# Schematic_328programmer.net
KiCad netlist of a schematic drawn in EAGLE
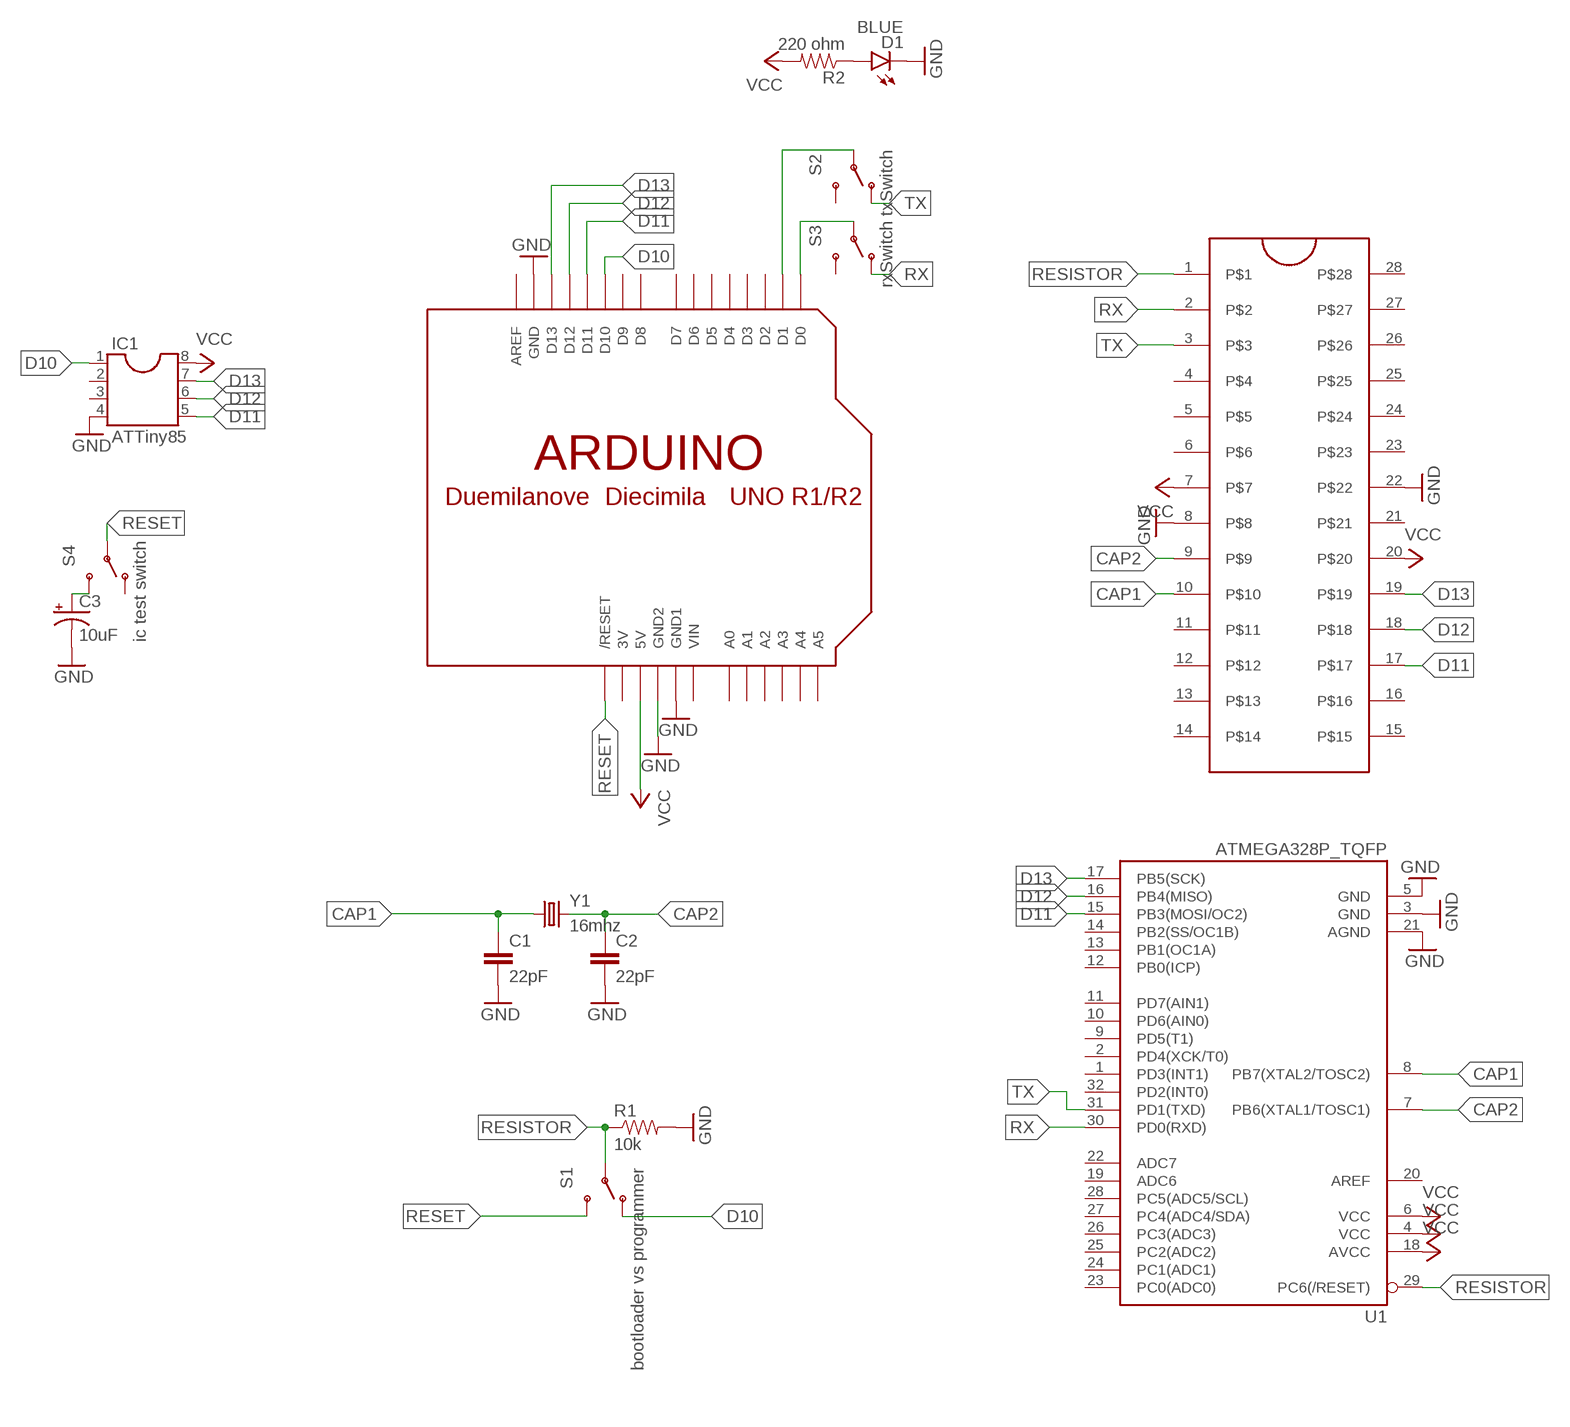
[diagram p0: schematic, sheet 1]

(export (version "E")
  (design (tool "Eeschema 10.0.6"))
  (components
    (comp (ref "C1")
      (value "22pF")
      (footprint "eagle-import:0603-CAP")
      (libsource (lib "eagle-import") (part "CAP0603-CAP"))
    )
    (comp (ref "C2")
      (value "22pF")
      (footprint "eagle-import:0603-CAP")
      (libsource (lib "eagle-import") (part "CAP0603-CAP"))
    )
    (comp (ref "C3")
      (value "10uF")
      (footprint "eagle-import:CPOL-RADIAL-10UF-25V")
      (libsource (lib "eagle-import") (part "10UF-25V-20%(PTH)"))
    )
    (comp (ref "D1")
      (value "BLUE")
      (footprint "eagle-import:LED-1206")
      (libsource (lib "eagle-import") (part "LED-BLUE1206"))
    )
    (comp (ref "IC1")
      (value "ATTiny85")
      (footprint "eagle-import:SOCKET-08")
      (libsource (lib "eagle-import") (part "DIL8S"))
    )
    (comp (ref "R1")
      (value "10k")
      (footprint "eagle-import:0603-RES")
      (libsource (lib "eagle-import") (part "RESISTOR0603-RES"))
    )
    (comp (ref "R2")
      (value "220 ohm")
      (footprint "eagle-import:0603-RES")
      (libsource (lib "eagle-import") (part "RESISTOR0603"))
    )
    (comp (ref "S1")
      (value "bootloader vs programmer")
      (footprint "eagle-import:SWITCH-SPDT")
      (libsource (lib "eagle-import") (part "SWITCH-SPDTPTH"))
    )
    (comp (ref "S2")
      (value "txSwitch")
      (footprint "eagle-import:SWITCH-SPDT")
      (libsource (lib "eagle-import") (part "SWITCH-SPDTPTH"))
    )
    (comp (ref "S3")
      (value "rxSwitch")
      (footprint "eagle-import:SWITCH-SPDT")
      (libsource (lib "eagle-import") (part "SWITCH-SPDTPTH"))
    )
    (comp (ref "S4")
      (value "ic test switch")
      (footprint "eagle-import:SWITCH-SPDT")
      (libsource (lib "eagle-import") (part "SWITCH-SPDTPTH"))
    )
    (comp (ref "U$1")
      (value "ARDUINO-NOHOLE")
      (footprint "eagle-import:ARDUINO-NOHOLE")
      (libsource (lib "eagle-import") (part "ARDUINO-NOHOLE"))
    )
    (comp (ref "U$3")
      (value "ZIFSOCKET-28-3ZIFFSOCKET-28-3")
      (footprint "eagle-import:DIL28-3-ZIF_SOCKET")
      (libsource (lib "eagle-import") (part "ZIFSOCKET-28-3ZIFFSOCKET-28-3"))
    )
    (comp (ref "U1")
      (value "ATMEGA328P_TQFP")
      (footprint "eagle-import:TQFP32-08")
      (libsource (lib "eagle-import") (part "ATMEGA328P_TQFP"))
    )
    (comp (ref "Y1")
      (value "16mhz")
      (footprint "eagle-import:HC49US")
      (libsource (lib "eagle-import") (part "CRYSTALHC49US"))
    )
  )
  (nets
    (net (code "1") (name "/3V") (class "Default")
      (node (ref "U$1") (pin "3V") (pinfunction "3V_3V") (pintype "power_in"))
    )
    (net (code "2") (name "/VIN") (class "Default")
      (node (ref "U$1") (pin "VIN") (pinfunction "VIN_VIN") (pintype "power_in"))
    )
    (net (code "3") (name "CAP1") (class "Default")
      (node (ref "C1") (pin "1") (pinfunction "1_1") (pintype "passive"))
      (node (ref "U$3") (pin "10") (pinfunction "P$10_10") (pintype "bidirectional"))
      (node (ref "U1") (pin "8") (pinfunction "PB7(XTAL2/TOSC2)_8") (pintype "bidirectional"))
      (node (ref "Y1") (pin "1") (pinfunction "1_1") (pintype "passive"))
    )
    (net (code "4") (name "CAP2") (class "Default")
      (node (ref "C2") (pin "1") (pinfunction "1_1") (pintype "passive"))
      (node (ref "U$3") (pin "9") (pinfunction "P$9_9") (pintype "bidirectional"))
      (node (ref "U1") (pin "7") (pinfunction "PB6(XTAL1/TOSC1)_7") (pintype "bidirectional"))
      (node (ref "Y1") (pin "2") (pinfunction "2_2") (pintype "passive"))
    )
    (net (code "5") (name "D10") (class "Default")
      (node (ref "IC1") (pin "1") (pinfunction "1_1") (pintype "passive"))
      (node (ref "S1") (pin "1") (pinfunction "O_1") (pintype "passive"))
      (node (ref "U$1") (pin "D10") (pinfunction "D10_D10") (pintype "bidirectional"))
    )
    (net (code "6") (name "D11") (class "Default")
      (node (ref "IC1") (pin "5") (pinfunction "5_5") (pintype "passive"))
      (node (ref "U$1") (pin "D11") (pinfunction "D11_D11") (pintype "bidirectional"))
      (node (ref "U$3") (pin "17") (pinfunction "P$17_17") (pintype "bidirectional"))
      (node (ref "U1") (pin "15") (pinfunction "PB3(MOSI/OC2)_15") (pintype "bidirectional"))
    )
    (net (code "7") (name "D12") (class "Default")
      (node (ref "IC1") (pin "6") (pinfunction "6_6") (pintype "passive"))
      (node (ref "U$1") (pin "D12") (pinfunction "D12_D12") (pintype "bidirectional"))
      (node (ref "U$3") (pin "18") (pinfunction "P$18_18") (pintype "bidirectional"))
      (node (ref "U1") (pin "16") (pinfunction "PB4(MISO)_16") (pintype "bidirectional"))
    )
    (net (code "8") (name "D13") (class "Default")
      (node (ref "IC1") (pin "7") (pinfunction "7_7") (pintype "passive"))
      (node (ref "U$1") (pin "D13") (pinfunction "D13_D13") (pintype "bidirectional"))
      (node (ref "U$3") (pin "19") (pinfunction "P$19_19") (pintype "bidirectional"))
      (node (ref "U1") (pin "17") (pinfunction "PB5(SCK)_17") (pintype "bidirectional"))
    )
    (net (code "9") (name "GND") (class "Default")
      (node (ref "C1") (pin "2") (pinfunction "2_2") (pintype "passive"))
      (node (ref "C2") (pin "2") (pinfunction "2_2") (pintype "passive"))
      (node (ref "C3") (pin "2") (pinfunction "-_2") (pintype "passive"))
      (node (ref "D1") (pin "C") (pinfunction "C_C") (pintype "passive"))
      (node (ref "IC1") (pin "4") (pinfunction "4_4") (pintype "passive"))
      (node (ref "R1") (pin "2") (pinfunction "2_2") (pintype "passive"))
      (node (ref "U$1") (pin "GND") (pinfunction "GND_GND") (pintype "power_in"))
      (node (ref "U$1") (pin "GND1") (pinfunction "GND1_GND1") (pintype "power_in"))
      (node (ref "U$1") (pin "GND2") (pinfunction "GND2_GND2") (pintype "power_in"))
      (node (ref "U$3") (pin "22") (pinfunction "P$22_22") (pintype "bidirectional"))
      (node (ref "U$3") (pin "8") (pinfunction "P$8_8") (pintype "bidirectional"))
      (node (ref "U1") (pin "21") (pinfunction "AGND_21") (pintype "bidirectional"))
      (node (ref "U1") (pin "3") (pinfunction "GND_3") (pintype "bidirectional"))
      (node (ref "U1") (pin "5") (pinfunction "GND_5") (pintype "bidirectional"))
    )
    (net (code "10") (name "Net-(C3-+)") (class "Default")
      (node (ref "C3") (pin "1") (pinfunction "+_1") (pintype "passive"))
      (node (ref "S4") (pin "3") (pinfunction "S_3") (pintype "passive"))
    )
    (net (code "11") (name "Net-(D1-PadA)") (class "Default")
      (node (ref "D1") (pin "A") (pinfunction "A_A") (pintype "passive"))
      (node (ref "R2") (pin "1") (pinfunction "1_1") (pintype "passive"))
    )
    (net (code "12") (name "Net-(S2-P)") (class "Default")
      (node (ref "S2") (pin "2") (pinfunction "P_2") (pintype "passive"))
      (node (ref "U$1") (pin "D1") (pinfunction "D1_D1") (pintype "bidirectional"))
    )
    (net (code "13") (name "Net-(S3-P)") (class "Default")
      (node (ref "S3") (pin "2") (pinfunction "P_2") (pintype "passive"))
      (node (ref "U$1") (pin "D0") (pinfunction "D0_D0") (pintype "bidirectional"))
    )
    (net (code "14") (name "RESET") (class "Default")
      (node (ref "S1") (pin "3") (pinfunction "S_3") (pintype "passive"))
      (node (ref "S4") (pin "2") (pinfunction "P_2") (pintype "passive"))
      (node (ref "U$1") (pin "RESET") (pinfunction "/RESET_RESET") (pintype "bidirectional"))
    )
    (net (code "15") (name "RESISTOR") (class "Default")
      (node (ref "R1") (pin "1") (pinfunction "1_1") (pintype "passive"))
      (node (ref "S1") (pin "2") (pinfunction "P_2") (pintype "passive"))
      (node (ref "U$3") (pin "1") (pinfunction "P$1_1") (pintype "bidirectional"))
      (node (ref "U1") (pin "29") (pinfunction "PC6(/RESET)_29") (pintype "bidirectional"))
    )
    (net (code "16") (name "RX") (class "Default")
      (node (ref "S3") (pin "1") (pinfunction "O_1") (pintype "passive"))
      (node (ref "U$3") (pin "2") (pinfunction "P$2_2") (pintype "bidirectional"))
      (node (ref "U1") (pin "30") (pinfunction "PD0(RXD)_30") (pintype "bidirectional"))
    )
    (net (code "17") (name "TX") (class "Default")
      (node (ref "S2") (pin "1") (pinfunction "O_1") (pintype "passive"))
      (node (ref "U$3") (pin "3") (pinfunction "P$3_3") (pintype "bidirectional"))
      (node (ref "U1") (pin "31") (pinfunction "PD1(TXD)_31") (pintype "bidirectional"))
    )
    (net (code "18") (name "VCC") (class "Default")
      (node (ref "IC1") (pin "8") (pinfunction "8_8") (pintype "passive"))
      (node (ref "R2") (pin "2") (pinfunction "2_2") (pintype "passive"))
      (node (ref "U$1") (pin "5V") (pinfunction "5V_5V") (pintype "power_in"))
      (node (ref "U$3") (pin "20") (pinfunction "P$20_20") (pintype "bidirectional"))
      (node (ref "U$3") (pin "7") (pinfunction "P$7_7") (pintype "bidirectional"))
      (node (ref "U1") (pin "18") (pinfunction "AVCC_18") (pintype "bidirectional"))
      (node (ref "U1") (pin "4") (pinfunction "VCC_4") (pintype "bidirectional"))
      (node (ref "U1") (pin "6") (pinfunction "VCC_6") (pintype "bidirectional"))
    )
    (net (code "19") (name "unconnected-(IC1-Pad2)") (class "Default")
      (node (ref "IC1") (pin "2") (pinfunction "2_2") (pintype "passive"))
    )
    (net (code "20") (name "unconnected-(IC1-Pad3)") (class "Default")
      (node (ref "IC1") (pin "3") (pinfunction "3_3") (pintype "passive"))
    )
    (net (code "21") (name "unconnected-(S2-S-Pad3)") (class "Default")
      (node (ref "S2") (pin "3") (pinfunction "S_3") (pintype "passive"))
    )
    (net (code "22") (name "unconnected-(S3-S-Pad3)") (class "Default")
      (node (ref "S3") (pin "3") (pinfunction "S_3") (pintype "passive"))
    )
    (net (code "23") (name "unconnected-(S4-O-Pad1)") (class "Default")
      (node (ref "S4") (pin "1") (pinfunction "O_1") (pintype "passive"))
    )
    (net (code "24") (name "unconnected-(U$1-PadA0)") (class "Default")
      (node (ref "U$1") (pin "A0") (pinfunction "A0_A0") (pintype "bidirectional"))
    )
    (net (code "25") (name "unconnected-(U$1-PadA1)") (class "Default")
      (node (ref "U$1") (pin "A1") (pinfunction "A1_A1") (pintype "bidirectional"))
    )
    (net (code "26") (name "unconnected-(U$1-PadA2)") (class "Default")
      (node (ref "U$1") (pin "A2") (pinfunction "A2_A2") (pintype "bidirectional"))
    )
    (net (code "27") (name "unconnected-(U$1-PadA3)") (class "Default")
      (node (ref "U$1") (pin "A3") (pinfunction "A3_A3") (pintype "bidirectional"))
    )
    (net (code "28") (name "unconnected-(U$1-PadA4)") (class "Default")
      (node (ref "U$1") (pin "A4") (pinfunction "A4_A4") (pintype "bidirectional"))
    )
    (net (code "29") (name "unconnected-(U$1-PadA5)") (class "Default")
      (node (ref "U$1") (pin "A5") (pinfunction "A5_A5") (pintype "bidirectional"))
    )
    (net (code "30") (name "unconnected-(U$1-PadAREF)") (class "Default")
      (node (ref "U$1") (pin "AREF") (pinfunction "AREF_AREF") (pintype "bidirectional"))
    )
    (net (code "31") (name "unconnected-(U$1-PadD2)") (class "Default")
      (node (ref "U$1") (pin "D2") (pinfunction "D2_D2") (pintype "bidirectional"))
    )
    (net (code "32") (name "unconnected-(U$1-PadD3)") (class "Default")
      (node (ref "U$1") (pin "D3") (pinfunction "D3_D3") (pintype "bidirectional"))
    )
    (net (code "33") (name "unconnected-(U$1-PadD4)") (class "Default")
      (node (ref "U$1") (pin "D4") (pinfunction "D4_D4") (pintype "bidirectional"))
    )
    (net (code "34") (name "unconnected-(U$1-PadD5)") (class "Default")
      (node (ref "U$1") (pin "D5") (pinfunction "D5_D5") (pintype "bidirectional"))
    )
    (net (code "35") (name "unconnected-(U$1-PadD6)") (class "Default")
      (node (ref "U$1") (pin "D6") (pinfunction "D6_D6") (pintype "bidirectional"))
    )
    (net (code "36") (name "unconnected-(U$1-PadD7)") (class "Default")
      (node (ref "U$1") (pin "D7") (pinfunction "D7_D7") (pintype "bidirectional"))
    )
    (net (code "37") (name "unconnected-(U$1-PadD8)") (class "Default")
      (node (ref "U$1") (pin "D8") (pinfunction "D8_D8") (pintype "bidirectional"))
    )
    (net (code "38") (name "unconnected-(U$1-PadD9)") (class "Default")
      (node (ref "U$1") (pin "D9") (pinfunction "D9_D9") (pintype "bidirectional"))
    )
    (net (code "39") (name "unconnected-(U$3-P$4-Pad4)") (class "Default")
      (node (ref "U$3") (pin "4") (pinfunction "P$4_4") (pintype "bidirectional"))
    )
    (net (code "40") (name "unconnected-(U$3-P$5-Pad5)") (class "Default")
      (node (ref "U$3") (pin "5") (pinfunction "P$5_5") (pintype "bidirectional"))
    )
    (net (code "41") (name "unconnected-(U$3-P$6-Pad6)") (class "Default")
      (node (ref "U$3") (pin "6") (pinfunction "P$6_6") (pintype "bidirectional"))
    )
    (net (code "42") (name "unconnected-(U$3-P$11-Pad11)") (class "Default")
      (node (ref "U$3") (pin "11") (pinfunction "P$11_11") (pintype "bidirectional"))
    )
    (net (code "43") (name "unconnected-(U$3-P$12-Pad12)") (class "Default")
      (node (ref "U$3") (pin "12") (pinfunction "P$12_12") (pintype "bidirectional"))
    )
    (net (code "44") (name "unconnected-(U$3-P$13-Pad13)") (class "Default")
      (node (ref "U$3") (pin "13") (pinfunction "P$13_13") (pintype "bidirectional"))
    )
    (net (code "45") (name "unconnected-(U$3-P$14-Pad14)") (class "Default")
      (node (ref "U$3") (pin "14") (pinfunction "P$14_14") (pintype "bidirectional"))
    )
    (net (code "46") (name "unconnected-(U$3-P$15-Pad15)") (class "Default")
      (node (ref "U$3") (pin "15") (pinfunction "P$15_15") (pintype "bidirectional"))
    )
    (net (code "47") (name "unconnected-(U$3-P$16-Pad16)") (class "Default")
      (node (ref "U$3") (pin "16") (pinfunction "P$16_16") (pintype "bidirectional"))
    )
    (net (code "48") (name "unconnected-(U$3-P$21-Pad21)") (class "Default")
      (node (ref "U$3") (pin "21") (pinfunction "P$21_21") (pintype "bidirectional"))
    )
    (net (code "49") (name "unconnected-(U$3-P$23-Pad23)") (class "Default")
      (node (ref "U$3") (pin "23") (pinfunction "P$23_23") (pintype "bidirectional"))
    )
    (net (code "50") (name "unconnected-(U$3-P$24-Pad24)") (class "Default")
      (node (ref "U$3") (pin "24") (pinfunction "P$24_24") (pintype "bidirectional"))
    )
    (net (code "51") (name "unconnected-(U$3-P$25-Pad25)") (class "Default")
      (node (ref "U$3") (pin "25") (pinfunction "P$25_25") (pintype "bidirectional"))
    )
    (net (code "52") (name "unconnected-(U$3-P$26-Pad26)") (class "Default")
      (node (ref "U$3") (pin "26") (pinfunction "P$26_26") (pintype "bidirectional"))
    )
    (net (code "53") (name "unconnected-(U$3-P$27-Pad27)") (class "Default")
      (node (ref "U$3") (pin "27") (pinfunction "P$27_27") (pintype "bidirectional"))
    )
    (net (code "54") (name "unconnected-(U$3-P$28-Pad28)") (class "Default")
      (node (ref "U$3") (pin "28") (pinfunction "P$28_28") (pintype "bidirectional"))
    )
    (net (code "55") (name "unconnected-(U1-ADC6-Pad19)") (class "Default")
      (node (ref "U1") (pin "19") (pinfunction "ADC6_19") (pintype "bidirectional"))
    )
    (net (code "56") (name "unconnected-(U1-ADC7-Pad22)") (class "Default")
      (node (ref "U1") (pin "22") (pinfunction "ADC7_22") (pintype "bidirectional"))
    )
    (net (code "57") (name "unconnected-(U1-AREF-Pad20)") (class "Default")
      (node (ref "U1") (pin "20") (pinfunction "AREF_20") (pintype "bidirectional"))
    )
    (net (code "58") (name "unconnected-(U1-PB0(ICP)-Pad12)") (class "Default")
      (node (ref "U1") (pin "12") (pinfunction "PB0(ICP)_12") (pintype "bidirectional"))
    )
    (net (code "59") (name "unconnected-(U1-PB1(OC1A)-Pad13)") (class "Default")
      (node (ref "U1") (pin "13") (pinfunction "PB1(OC1A)_13") (pintype "bidirectional"))
    )
    (net (code "60") (name "unconnected-(U1-PB2(SS{slash}OC1B)-Pad14)") (class "Default")
      (node (ref "U1") (pin "14") (pinfunction "PB2(SS/OC1B)_14") (pintype "bidirectional"))
    )
    (net (code "61") (name "unconnected-(U1-PC0(ADC0)-Pad23)") (class "Default")
      (node (ref "U1") (pin "23") (pinfunction "PC0(ADC0)_23") (pintype "bidirectional"))
    )
    (net (code "62") (name "unconnected-(U1-PC1(ADC1)-Pad24)") (class "Default")
      (node (ref "U1") (pin "24") (pinfunction "PC1(ADC1)_24") (pintype "bidirectional"))
    )
    (net (code "63") (name "unconnected-(U1-PC2(ADC2)-Pad25)") (class "Default")
      (node (ref "U1") (pin "25") (pinfunction "PC2(ADC2)_25") (pintype "bidirectional"))
    )
    (net (code "64") (name "unconnected-(U1-PC3(ADC3)-Pad26)") (class "Default")
      (node (ref "U1") (pin "26") (pinfunction "PC3(ADC3)_26") (pintype "bidirectional"))
    )
    (net (code "65") (name "unconnected-(U1-PC4(ADC4{slash}SDA)-Pad27)") (class "Default")
      (node (ref "U1") (pin "27") (pinfunction "PC4(ADC4/SDA)_27") (pintype "bidirectional"))
    )
    (net (code "66") (name "unconnected-(U1-PC5(ADC5{slash}SCL)-Pad28)") (class "Default")
      (node (ref "U1") (pin "28") (pinfunction "PC5(ADC5/SCL)_28") (pintype "bidirectional"))
    )
    (net (code "67") (name "unconnected-(U1-PD2(INT0)-Pad32)") (class "Default")
      (node (ref "U1") (pin "32") (pinfunction "PD2(INT0)_32") (pintype "bidirectional"))
    )
    (net (code "68") (name "unconnected-(U1-PD3(INT1)-Pad1)") (class "Default")
      (node (ref "U1") (pin "1") (pinfunction "PD3(INT1)_1") (pintype "bidirectional"))
    )
    (net (code "69") (name "unconnected-(U1-PD4(XCK{slash}T0)-Pad2)") (class "Default")
      (node (ref "U1") (pin "2") (pinfunction "PD4(XCK/T0)_2") (pintype "bidirectional"))
    )
    (net (code "70") (name "unconnected-(U1-PD5(T1)-Pad9)") (class "Default")
      (node (ref "U1") (pin "9") (pinfunction "PD5(T1)_9") (pintype "bidirectional"))
    )
    (net (code "71") (name "unconnected-(U1-PD6(AIN0)-Pad10)") (class "Default")
      (node (ref "U1") (pin "10") (pinfunction "PD6(AIN0)_10") (pintype "bidirectional"))
    )
    (net (code "72") (name "unconnected-(U1-PD7(AIN1)-Pad11)") (class "Default")
      (node (ref "U1") (pin "11") (pinfunction "PD7(AIN1)_11") (pintype "bidirectional"))
    )
  )
)
